# Sheet3.net
KiCad netlist of a schematic drawn in Altium Designer
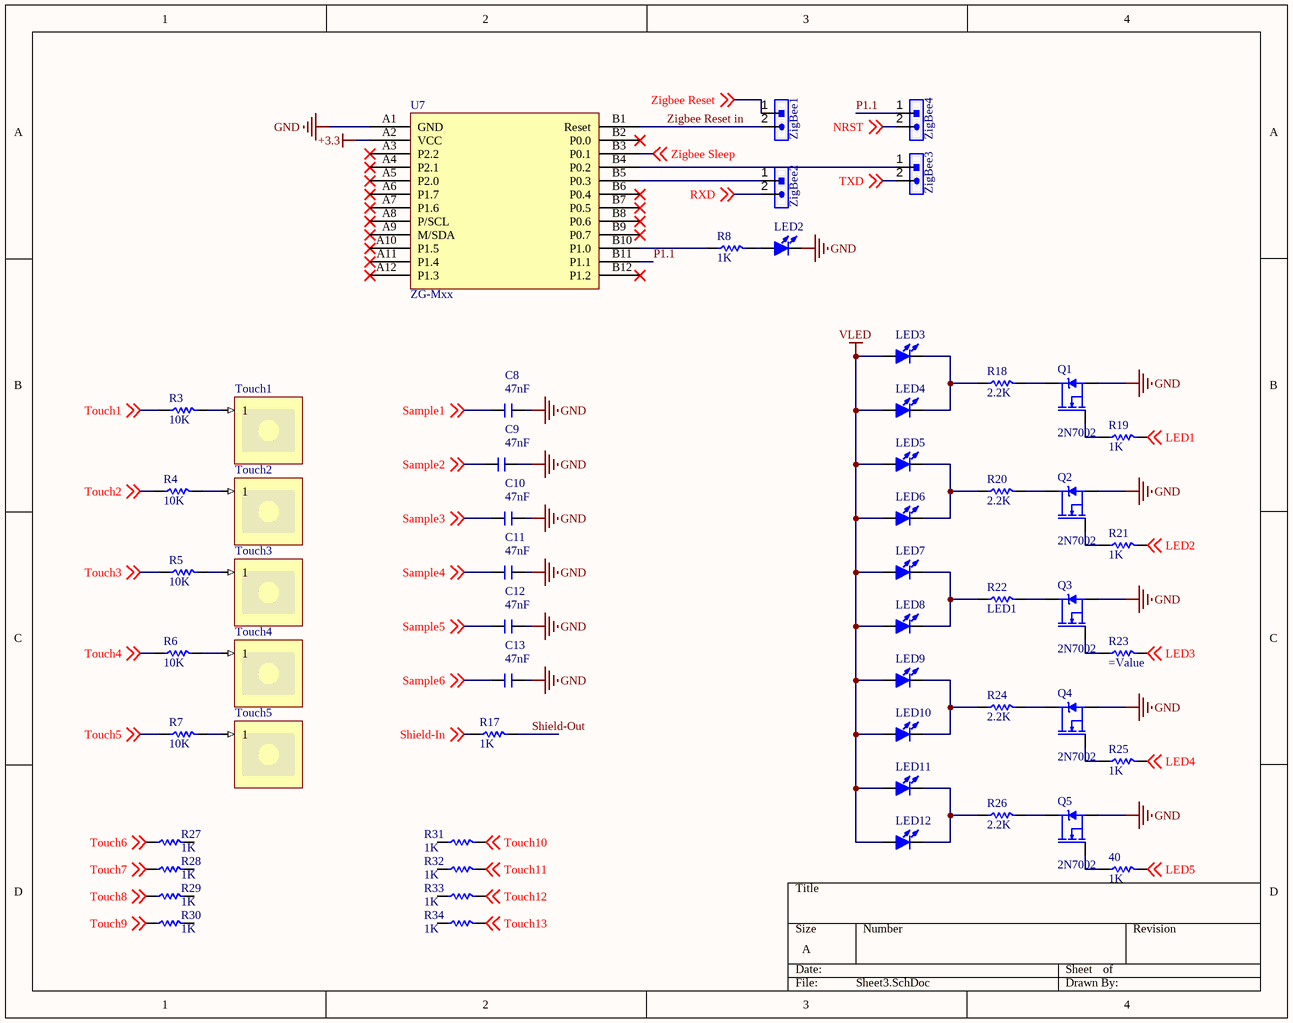
[diagram p0: Sheet3.SchDoc]

(export (version "E")
  (design (tool "Eeschema 10.0.6"))
  (components
    (comp (ref "40")
      (value "1K")
      (footprint "R 0805")
      (description "Chip resistor")
      (fields (field (name "版权归属") "源创客"))
      (libsource (lib "Passive (Resistor-Capacitor-Inductor-Veristor-Ferrite)") (part "R"))
    )
    (comp (ref "C8")
      (value "47nF")
      (footprint "C 0805")
      (description "Non-polar patch capacitor")
      (fields (field (name "版权归属") "源创客"))
      (libsource (lib "Passive (Resistor-Capacitor-Inductor-Veristor-Ferrite)") (part "C"))
    )
    (comp (ref "C9")
      (value "47nF")
      (footprint "C 0805")
      (description "Non-polar patch capacitor")
      (fields (field (name "版权归属") "源创客"))
      (libsource (lib "Passive (Resistor-Capacitor-Inductor-Veristor-Ferrite)") (part "C"))
    )
    (comp (ref "C10")
      (value "47nF")
      (footprint "C 0805")
      (description "Non-polar patch capacitor")
      (fields (field (name "版权归属") "源创客"))
      (libsource (lib "Passive (Resistor-Capacitor-Inductor-Veristor-Ferrite)") (part "C"))
    )
    (comp (ref "C11")
      (value "47nF")
      (footprint "C 0805")
      (description "Non-polar patch capacitor")
      (fields (field (name "版权归属") "源创客"))
      (libsource (lib "Passive (Resistor-Capacitor-Inductor-Veristor-Ferrite)") (part "C"))
    )
    (comp (ref "C12")
      (value "47nF")
      (footprint "C 0805")
      (description "Non-polar patch capacitor")
      (fields (field (name "版权归属") "源创客"))
      (libsource (lib "Passive (Resistor-Capacitor-Inductor-Veristor-Ferrite)") (part "C"))
    )
    (comp (ref "C13")
      (value "47nF")
      (footprint "C 0805")
      (description "Non-polar patch capacitor")
      (fields (field (name "版权归属") "源创客"))
      (libsource (lib "Passive (Resistor-Capacitor-Inductor-Veristor-Ferrite)") (part "C"))
    )
    (comp (ref "LED2")
      (value "LED-SMD")
      (footprint "LED 0805B")
      (description "Patch LED")
      (fields (field (name "版权归属") "源创客"))
      (libsource (lib "LED") (part "LED-SMD"))
    )
    (comp (ref "LED3")
      (value "~")
      (footprint "LED 3MM-B")
      (description "Plug-in LED")
      (fields (field (name "版权归属") "源创客"))
      (libsource (lib "LED") (part "LED-3MM"))
    )
    (comp (ref "LED4")
      (value "~")
      (footprint "LED 3MM-B")
      (description "Plug-in LED")
      (fields (field (name "版权归属") "源创客"))
      (libsource (lib "LED") (part "LED-3MM"))
    )
    (comp (ref "LED5")
      (value "~")
      (footprint "LED 3MM-B")
      (description "Plug-in LED")
      (fields (field (name "版权归属") "源创客"))
      (libsource (lib "LED") (part "LED-3MM"))
    )
    (comp (ref "LED6")
      (value "~")
      (footprint "LED 3MM-B")
      (description "Plug-in LED")
      (fields (field (name "版权归属") "源创客"))
      (libsource (lib "LED") (part "LED-3MM"))
    )
    (comp (ref "LED7")
      (value "~")
      (footprint "LED 3MM-B")
      (description "Plug-in LED")
      (fields (field (name "版权归属") "源创客"))
      (libsource (lib "LED") (part "LED-3MM"))
    )
    (comp (ref "LED8")
      (value "~")
      (footprint "LED 3MM-B")
      (description "Plug-in LED")
      (fields (field (name "版权归属") "源创客"))
      (libsource (lib "LED") (part "LED-3MM"))
    )
    (comp (ref "LED9")
      (value "~")
      (footprint "LED 3MM-B")
      (description "Plug-in LED")
      (fields (field (name "版权归属") "源创客"))
      (libsource (lib "LED") (part "LED-3MM"))
    )
    (comp (ref "LED10")
      (value "~")
      (footprint "LED 3MM-B")
      (description "Plug-in LED")
      (fields (field (name "版权归属") "源创客"))
      (libsource (lib "LED") (part "LED-3MM"))
    )
    (comp (ref "LED11")
      (value "~")
      (footprint "LED 3MM-B")
      (description "Plug-in LED")
      (fields (field (name "版权归属") "源创客"))
      (libsource (lib "LED") (part "LED-3MM"))
    )
    (comp (ref "LED12")
      (value "~")
      (footprint "LED 3MM-B")
      (description "Plug-in LED")
      (fields (field (name "版权归属") "源创客"))
      (libsource (lib "LED") (part "LED-3MM"))
    )
    (comp (ref "Q1")
      (value "2N7002")
      (footprint "SOT23-3")
      (description "N-Channel 60V 115mA (Tc) 225mW (Ta) Surface Mount SOT-23-3 (TO-236)")
      (fields (field (name "MF") "STMicroelectronics"))
      (libsource (lib "2N7002") (part "2N7002"))
    )
    (comp (ref "Q2")
      (value "2N7002")
      (footprint "SOT23-3")
      (description "N-Channel 60V 115mA (Tc) 225mW (Ta) Surface Mount SOT-23-3 (TO-236)")
      (fields (field (name "MF") "STMicroelectronics"))
      (libsource (lib "2N7002") (part "2N7002"))
    )
    (comp (ref "Q3")
      (value "2N7002")
      (footprint "SOT23-3")
      (description "N-Channel 60V 115mA (Tc) 225mW (Ta) Surface Mount SOT-23-3 (TO-236)")
      (fields (field (name "MF") "STMicroelectronics"))
      (libsource (lib "2N7002") (part "2N7002"))
    )
    (comp (ref "Q4")
      (value "2N7002")
      (footprint "SOT23-3")
      (description "N-Channel 60V 115mA (Tc) 225mW (Ta) Surface Mount SOT-23-3 (TO-236)")
      (fields (field (name "MF") "STMicroelectronics"))
      (libsource (lib "2N7002") (part "2N7002"))
    )
    (comp (ref "Q5")
      (value "2N7002")
      (footprint "SOT23-3")
      (description "N-Channel 60V 115mA (Tc) 225mW (Ta) Surface Mount SOT-23-3 (TO-236)")
      (fields (field (name "MF") "STMicroelectronics"))
      (libsource (lib "2N7002") (part "2N7002"))
    )
    (comp (ref "R3")
      (value "10K")
      (footprint "R 0805")
      (description "Chip resistor")
      (fields (field (name "版权归属") "源创客"))
      (libsource (lib "Passive (Resistor-Capacitor-Inductor-Veristor-Ferrite)") (part "R"))
    )
    (comp (ref "R4")
      (value "10K")
      (footprint "R 0805")
      (description "Chip resistor")
      (fields (field (name "版权归属") "源创客"))
      (libsource (lib "Passive (Resistor-Capacitor-Inductor-Veristor-Ferrite)") (part "R"))
    )
    (comp (ref "R5")
      (value "10K")
      (footprint "R 0805")
      (description "Chip resistor")
      (fields (field (name "版权归属") "源创客"))
      (libsource (lib "Passive (Resistor-Capacitor-Inductor-Veristor-Ferrite)") (part "R"))
    )
    (comp (ref "R6")
      (value "10K")
      (footprint "R 0805")
      (description "Chip resistor")
      (fields (field (name "版权归属") "源创客"))
      (libsource (lib "Passive (Resistor-Capacitor-Inductor-Veristor-Ferrite)") (part "R"))
    )
    (comp (ref "R7")
      (value "10K")
      (footprint "R 0805")
      (description "Chip resistor")
      (fields (field (name "版权归属") "源创客"))
      (libsource (lib "Passive (Resistor-Capacitor-Inductor-Veristor-Ferrite)") (part "R"))
    )
    (comp (ref "R8")
      (value "1K")
      (footprint "R 0805")
      (description "Chip resistor")
      (fields (field (name "版权归属") "源创客"))
      (libsource (lib "Passive (Resistor-Capacitor-Inductor-Veristor-Ferrite)") (part "R"))
    )
    (comp (ref "R17")
      (value "1K")
      (footprint "R 0805")
      (description "Chip resistor")
      (fields (field (name "版权归属") "源创客"))
      (libsource (lib "Passive (Resistor-Capacitor-Inductor-Veristor-Ferrite)") (part "R"))
    )
    (comp (ref "R18")
      (value "2.2K")
      (footprint "R 0805")
      (description "Chip resistor")
      (fields (field (name "版权归属") "源创客"))
      (libsource (lib "Passive (Resistor-Capacitor-Inductor-Veristor-Ferrite)") (part "R"))
    )
    (comp (ref "R19")
      (value "1K")
      (footprint "R 0805")
      (description "Chip resistor")
      (fields (field (name "版权归属") "源创客"))
      (libsource (lib "Passive (Resistor-Capacitor-Inductor-Veristor-Ferrite)") (part "R"))
    )
    (comp (ref "R20")
      (value "2.2K")
      (footprint "R 0805")
      (description "Chip resistor")
      (fields (field (name "版权归属") "源创客"))
      (libsource (lib "Passive (Resistor-Capacitor-Inductor-Veristor-Ferrite)") (part "R"))
    )
    (comp (ref "R21")
      (value "1K")
      (footprint "R 0805")
      (description "Chip resistor")
      (fields (field (name "版权归属") "源创客"))
      (libsource (lib "Passive (Resistor-Capacitor-Inductor-Veristor-Ferrite)") (part "R"))
    )
    (comp (ref "R22")
      (value "LED1")
      (footprint "R 0805")
      (description "Chip resistor")
      (fields (field (name "版权归属") "源创客"))
      (libsource (lib "Passive (Resistor-Capacitor-Inductor-Veristor-Ferrite)") (part "R"))
    )
    (comp (ref "R23")
      (value "~")
      (footprint "R 0805")
      (description "Chip resistor")
      (fields (field (name "版权归属") "源创客"))
      (libsource (lib "Passive (Resistor-Capacitor-Inductor-Veristor-Ferrite)") (part "R"))
    )
    (comp (ref "R24")
      (value "2.2K")
      (footprint "R 0805")
      (description "Chip resistor")
      (fields (field (name "版权归属") "源创客"))
      (libsource (lib "Passive (Resistor-Capacitor-Inductor-Veristor-Ferrite)") (part "R"))
    )
    (comp (ref "R25")
      (value "1K")
      (footprint "R 0805")
      (description "Chip resistor")
      (fields (field (name "版权归属") "源创客"))
      (libsource (lib "Passive (Resistor-Capacitor-Inductor-Veristor-Ferrite)") (part "R"))
    )
    (comp (ref "R26")
      (value "2.2K")
      (footprint "R 0805")
      (description "Chip resistor")
      (fields (field (name "版权归属") "源创客"))
      (libsource (lib "Passive (Resistor-Capacitor-Inductor-Veristor-Ferrite)") (part "R"))
    )
    (comp (ref "R27")
      (value "1K")
      (footprint "R 0805")
      (description "Chip resistor")
      (fields (field (name "版权归属") "源创客"))
      (libsource (lib "Passive (Resistor-Capacitor-Inductor-Veristor-Ferrite)") (part "R"))
    )
    (comp (ref "R28")
      (value "1K")
      (footprint "R 0805")
      (description "Chip resistor")
      (fields (field (name "版权归属") "源创客"))
      (libsource (lib "Passive (Resistor-Capacitor-Inductor-Veristor-Ferrite)") (part "R"))
    )
    (comp (ref "R29")
      (value "1K")
      (footprint "R 0805")
      (description "Chip resistor")
      (fields (field (name "版权归属") "源创客"))
      (libsource (lib "Passive (Resistor-Capacitor-Inductor-Veristor-Ferrite)") (part "R"))
    )
    (comp (ref "R30")
      (value "1K")
      (footprint "R 0805")
      (description "Chip resistor")
      (fields (field (name "版权归属") "源创客"))
      (libsource (lib "Passive (Resistor-Capacitor-Inductor-Veristor-Ferrite)") (part "R"))
    )
    (comp (ref "R31")
      (value "1K")
      (footprint "R 0805")
      (description "Chip resistor")
      (fields (field (name "版权归属") "源创客"))
      (libsource (lib "Passive (Resistor-Capacitor-Inductor-Veristor-Ferrite)") (part "R"))
    )
    (comp (ref "R32")
      (value "1K")
      (footprint "R 0805")
      (description "Chip resistor")
      (fields (field (name "版权归属") "源创客"))
      (libsource (lib "Passive (Resistor-Capacitor-Inductor-Veristor-Ferrite)") (part "R"))
    )
    (comp (ref "R33")
      (value "1K")
      (footprint "R 0805")
      (description "Chip resistor")
      (fields (field (name "版权归属") "源创客"))
      (libsource (lib "Passive (Resistor-Capacitor-Inductor-Veristor-Ferrite)") (part "R"))
    )
    (comp (ref "R34")
      (value "1K")
      (footprint "R 0805")
      (description "Chip resistor")
      (fields (field (name "版权归属") "源创客"))
      (libsource (lib "Passive (Resistor-Capacitor-Inductor-Veristor-Ferrite)") (part "R"))
    )
    (comp (ref "Touch1")
      (value "CircularButton")
      (libsource (lib "Cypress CapSense") (part "CircularButton"))
    )
    (comp (ref "Touch2")
      (value "CircularButton")
      (libsource (lib "Cypress CapSense") (part "CircularButton"))
    )
    (comp (ref "Touch3")
      (value "CircularButton")
      (libsource (lib "Cypress CapSense") (part "CircularButton"))
    )
    (comp (ref "Touch4")
      (value "CircularButton")
      (libsource (lib "Cypress CapSense") (part "CircularButton"))
    )
    (comp (ref "Touch5")
      (value "CircularButton")
      (libsource (lib "Cypress CapSense") (part "CircularButton"))
    )
    (comp (ref "U7") (value "ZG-Mxx") (footprint "XBee") (libsource (lib "XBee") (part "XBee")))
    (comp (ref "ZigBee1")
      (value "HDR-1X2")
      (footprint "HDR-1X2")
      (description "2P Connector")
      (fields (field (name "版权归属") "源创客"))
      (libsource (lib "Connectors") (part "Header 2"))
    )
    (comp (ref "ZigBee2")
      (value "HDR-1X2")
      (footprint "HDR-1X2")
      (description "2P Connector")
      (fields (field (name "版权归属") "源创客"))
      (libsource (lib "Connectors") (part "Header 2"))
    )
    (comp (ref "ZigBee3")
      (value "HDR-1X2")
      (footprint "HDR-1X2")
      (description "2P Connector")
      (fields (field (name "版权归属") "源创客"))
      (libsource (lib "Connectors") (part "Header 2"))
    )
    (comp (ref "ZigBee4")
      (value "HDR-1X2")
      (footprint "HDR-1X2")
      (description "2P Connector")
      (fields (field (name "版权归属") "源创客"))
      (libsource (lib "Connectors") (part "Header 2"))
    )
  )
  (nets
    (net (code "1") (name "+3.3") (class "Default")
      (node (ref "U7") (pin "A2") (pinfunction "VCC_A2") (pintype "passive"))
    )
    (net (code "2") (name "/P1.1") (class "Default")
      (node (ref "U7") (pin "B11") (pinfunction "P1.1_B11") (pintype "passive"))
      (node (ref "ZigBee4") (pin "1") (pintype "passive"))
    )
    (net (code "3") (name "/Shield-Out") (class "Default")
      (node (ref "R17") (pin "2") (pinfunction "2_2") (pintype "passive"))
    )
    (net (code "4") (name "/Zigbee Reset in") (class "Default")
      (node (ref "U7") (pin "B1") (pinfunction "Reset_B1") (pintype "passive"))
      (node (ref "ZigBee1") (pin "2") (pintype "passive"))
    )
    (net (code "5") (name "GND") (class "Default")
      (node (ref "C10") (pin "2") (pinfunction "2_2") (pintype "passive"))
      (node (ref "C11") (pin "2") (pinfunction "2_2") (pintype "passive"))
      (node (ref "C12") (pin "2") (pinfunction "2_2") (pintype "passive"))
      (node (ref "C13") (pin "2") (pinfunction "2_2") (pintype "passive"))
      (node (ref "C8") (pin "2") (pinfunction "2_2") (pintype "passive"))
      (node (ref "C9") (pin "2") (pinfunction "2_2") (pintype "passive"))
      (node (ref "LED2") (pin "2") (pinfunction "K_2") (pintype "passive"))
      (node (ref "Q1") (pin "2") (pinfunction "S_2") (pintype "bidirectional"))
      (node (ref "Q2") (pin "2") (pinfunction "S_2") (pintype "bidirectional"))
      (node (ref "Q3") (pin "2") (pinfunction "S_2") (pintype "bidirectional"))
      (node (ref "Q4") (pin "2") (pinfunction "S_2") (pintype "bidirectional"))
      (node (ref "Q5") (pin "2") (pinfunction "S_2") (pintype "bidirectional"))
      (node (ref "U7") (pin "A1") (pinfunction "GND_A1") (pintype "passive"))
    )
    (net (code "6") (name "LED1") (class "Default")
      (node (ref "R19") (pin "2") (pinfunction "2_2") (pintype "passive"))
    )
    (net (code "7") (name "LED2") (class "Default")
      (node (ref "R21") (pin "2") (pinfunction "2_2") (pintype "passive"))
    )
    (net (code "8") (name "LED3") (class "Default")
      (node (ref "R23") (pin "2") (pinfunction "2_2") (pintype "passive"))
    )
    (net (code "9") (name "LED4") (class "Default")
      (node (ref "R25") (pin "2") (pinfunction "2_2") (pintype "passive"))
    )
    (net (code "10") (name "LED5") (class "Default")
      (node (ref "40") (pin "2") (pinfunction "2_2") (pintype "passive"))
    )
    (net (code "11") (name "NRST") (class "Default") (node (ref "ZigBee4") (pin "2") (pintype "passive")))
    (net (code "12") (name "Net-(LED2-A)") (class "Default")
      (node (ref "LED2") (pin "1") (pinfunction "A_1") (pintype "passive"))
      (node (ref "R8") (pin "2") (pinfunction "2_2") (pintype "passive"))
    )
    (net (code "13") (name "Net-(LED3-K)") (class "Default")
      (node (ref "LED3") (pin "2") (pinfunction "K_2") (pintype "passive"))
      (node (ref "LED4") (pin "2") (pinfunction "K_2") (pintype "passive"))
      (node (ref "R18") (pin "1") (pinfunction "1_1") (pintype "passive"))
    )
    (net (code "14") (name "Net-(LED5-K)") (class "Default")
      (node (ref "LED5") (pin "2") (pinfunction "K_2") (pintype "passive"))
      (node (ref "LED6") (pin "2") (pinfunction "K_2") (pintype "passive"))
      (node (ref "R20") (pin "1") (pinfunction "1_1") (pintype "passive"))
    )
    (net (code "15") (name "Net-(LED7-K)") (class "Default")
      (node (ref "LED7") (pin "2") (pinfunction "K_2") (pintype "passive"))
      (node (ref "LED8") (pin "2") (pinfunction "K_2") (pintype "passive"))
      (node (ref "R22") (pin "1") (pinfunction "1_1") (pintype "passive"))
    )
    (net (code "16") (name "Net-(LED10-K)") (class "Default")
      (node (ref "LED10") (pin "2") (pinfunction "K_2") (pintype "passive"))
      (node (ref "LED9") (pin "2") (pinfunction "K_2") (pintype "passive"))
      (node (ref "R24") (pin "1") (pinfunction "1_1") (pintype "passive"))
    )
    (net (code "17") (name "Net-(LED11-K)") (class "Default")
      (node (ref "LED11") (pin "2") (pinfunction "K_2") (pintype "passive"))
      (node (ref "LED12") (pin "2") (pinfunction "K_2") (pintype "passive"))
      (node (ref "R26") (pin "1") (pinfunction "1_1") (pintype "passive"))
    )
    (net (code "18") (name "Net-(Q1-D)") (class "Default")
      (node (ref "Q1") (pin "3") (pinfunction "D_3") (pintype "bidirectional"))
      (node (ref "R18") (pin "2") (pinfunction "2_2") (pintype "passive"))
    )
    (net (code "19") (name "Net-(Q1-G)") (class "Default")
      (node (ref "Q1") (pin "1") (pinfunction "G_1") (pintype "bidirectional"))
      (node (ref "R19") (pin "1") (pinfunction "1_1") (pintype "passive"))
    )
    (net (code "20") (name "Net-(Q2-D)") (class "Default")
      (node (ref "Q2") (pin "3") (pinfunction "D_3") (pintype "bidirectional"))
      (node (ref "R20") (pin "2") (pinfunction "2_2") (pintype "passive"))
    )
    (net (code "21") (name "Net-(Q2-G)") (class "Default")
      (node (ref "Q2") (pin "1") (pinfunction "G_1") (pintype "bidirectional"))
      (node (ref "R21") (pin "1") (pinfunction "1_1") (pintype "passive"))
    )
    (net (code "22") (name "Net-(Q3-D)") (class "Default")
      (node (ref "Q3") (pin "3") (pinfunction "D_3") (pintype "bidirectional"))
      (node (ref "R22") (pin "2") (pinfunction "2_2") (pintype "passive"))
    )
    (net (code "23") (name "Net-(Q3-G)") (class "Default")
      (node (ref "Q3") (pin "1") (pinfunction "G_1") (pintype "bidirectional"))
      (node (ref "R23") (pin "1") (pinfunction "1_1") (pintype "passive"))
    )
    (net (code "24") (name "Net-(Q4-D)") (class "Default")
      (node (ref "Q4") (pin "3") (pinfunction "D_3") (pintype "bidirectional"))
      (node (ref "R24") (pin "2") (pinfunction "2_2") (pintype "passive"))
    )
    (net (code "25") (name "Net-(Q4-G)") (class "Default")
      (node (ref "Q4") (pin "1") (pinfunction "G_1") (pintype "bidirectional"))
      (node (ref "R25") (pin "1") (pinfunction "1_1") (pintype "passive"))
    )
    (net (code "26") (name "Net-(Q5-D)") (class "Default")
      (node (ref "Q5") (pin "3") (pinfunction "D_3") (pintype "bidirectional"))
      (node (ref "R26") (pin "2") (pinfunction "2_2") (pintype "passive"))
    )
    (net (code "27") (name "Net-(Q5-G)") (class "Default")
      (node (ref "40") (pin "1") (pinfunction "1_1") (pintype "passive"))
      (node (ref "Q5") (pin "1") (pinfunction "G_1") (pintype "bidirectional"))
    )
    (net (code "28") (name "Net-(R3-Pad2)") (class "Default")
      (node (ref "R3") (pin "2") (pinfunction "2_2") (pintype "passive"))
      (node (ref "Touch1") (pin "1") (pinfunction "1_1") (pintype "input"))
    )
    (net (code "29") (name "Net-(R4-Pad2)") (class "Default")
      (node (ref "R4") (pin "2") (pinfunction "2_2") (pintype "passive"))
      (node (ref "Touch2") (pin "1") (pinfunction "1_1") (pintype "input"))
    )
    (net (code "30") (name "Net-(R5-Pad2)") (class "Default")
      (node (ref "R5") (pin "2") (pinfunction "2_2") (pintype "passive"))
      (node (ref "Touch3") (pin "1") (pinfunction "1_1") (pintype "input"))
    )
    (net (code "31") (name "Net-(R6-Pad2)") (class "Default")
      (node (ref "R6") (pin "2") (pinfunction "2_2") (pintype "passive"))
      (node (ref "Touch4") (pin "1") (pinfunction "1_1") (pintype "input"))
    )
    (net (code "32") (name "Net-(R7-Pad2)") (class "Default")
      (node (ref "R7") (pin "2") (pinfunction "2_2") (pintype "passive"))
      (node (ref "Touch5") (pin "1") (pinfunction "1_1") (pintype "input"))
    )
    (net (code "33") (name "Net-(U7-P0.2)") (class "Default")
      (node (ref "U7") (pin "B4") (pinfunction "P0.2_B4") (pintype "passive"))
      (node (ref "ZigBee3") (pin "1") (pintype "passive"))
    )
    (net (code "34") (name "Net-(U7-P0.3)") (class "Default")
      (node (ref "U7") (pin "B5") (pinfunction "P0.3_B5") (pintype "passive"))
      (node (ref "ZigBee2") (pin "1") (pintype "passive"))
    )
    (net (code "35") (name "Net-(U7-P1.0)") (class "Default")
      (node (ref "R8") (pin "1") (pinfunction "1_1") (pintype "passive"))
      (node (ref "U7") (pin "B10") (pinfunction "P1.0_B10") (pintype "passive"))
    )
    (net (code "36") (name "RXD") (class "Default") (node (ref "ZigBee2") (pin "2") (pintype "passive")))
    (net (code "37") (name "Sample1") (class "Default")
      (node (ref "C8") (pin "1") (pinfunction "1_1") (pintype "passive"))
    )
    (net (code "38") (name "Sample2") (class "Default")
      (node (ref "C9") (pin "1") (pinfunction "1_1") (pintype "passive"))
    )
    (net (code "39") (name "Sample3") (class "Default")
      (node (ref "C10") (pin "1") (pinfunction "1_1") (pintype "passive"))
    )
    (net (code "40") (name "Sample4") (class "Default")
      (node (ref "C11") (pin "1") (pinfunction "1_1") (pintype "passive"))
    )
    (net (code "41") (name "Sample5") (class "Default")
      (node (ref "C12") (pin "1") (pinfunction "1_1") (pintype "passive"))
    )
    (net (code "42") (name "Sample6") (class "Default")
      (node (ref "C13") (pin "1") (pinfunction "1_1") (pintype "passive"))
    )
    (net (code "43") (name "Shield-In") (class "Default")
      (node (ref "R17") (pin "1") (pinfunction "1_1") (pintype "passive"))
    )
    (net (code "44") (name "TXD") (class "Default") (node (ref "ZigBee3") (pin "2") (pintype "passive")))
    (net (code "45") (name "Touch1") (class "Default")
      (node (ref "R3") (pin "1") (pinfunction "1_1") (pintype "passive"))
    )
    (net (code "46") (name "Touch2") (class "Default")
      (node (ref "R4") (pin "1") (pinfunction "1_1") (pintype "passive"))
    )
    (net (code "47") (name "Touch3") (class "Default")
      (node (ref "R5") (pin "1") (pinfunction "1_1") (pintype "passive"))
    )
    (net (code "48") (name "Touch4") (class "Default")
      (node (ref "R6") (pin "1") (pinfunction "1_1") (pintype "passive"))
    )
    (net (code "49") (name "Touch5") (class "Default")
      (node (ref "R7") (pin "1") (pinfunction "1_1") (pintype "passive"))
    )
    (net (code "50") (name "Touch6") (class "Default")
      (node (ref "R27") (pin "1") (pinfunction "1_1") (pintype "passive"))
    )
    (net (code "51") (name "Touch7") (class "Default")
      (node (ref "R28") (pin "1") (pinfunction "1_1") (pintype "passive"))
    )
    (net (code "52") (name "Touch8") (class "Default")
      (node (ref "R29") (pin "1") (pinfunction "1_1") (pintype "passive"))
    )
    (net (code "53") (name "Touch9") (class "Default")
      (node (ref "R30") (pin "1") (pinfunction "1_1") (pintype "passive"))
    )
    (net (code "54") (name "Touch10") (class "Default")
      (node (ref "R31") (pin "2") (pinfunction "2_2") (pintype "passive"))
    )
    (net (code "55") (name "Touch11") (class "Default")
      (node (ref "R32") (pin "2") (pinfunction "2_2") (pintype "passive"))
    )
    (net (code "56") (name "Touch12") (class "Default")
      (node (ref "R33") (pin "2") (pinfunction "2_2") (pintype "passive"))
    )
    (net (code "57") (name "Touch13") (class "Default")
      (node (ref "R34") (pin "2") (pinfunction "2_2") (pintype "passive"))
    )
    (net (code "58") (name "VLED") (class "Default")
      (node (ref "LED10") (pin "1") (pinfunction "A_1") (pintype "passive"))
      (node (ref "LED11") (pin "1") (pinfunction "A_1") (pintype "passive"))
      (node (ref "LED12") (pin "1") (pinfunction "A_1") (pintype "passive"))
      (node (ref "LED3") (pin "1") (pinfunction "A_1") (pintype "passive"))
      (node (ref "LED4") (pin "1") (pinfunction "A_1") (pintype "passive"))
      (node (ref "LED5") (pin "1") (pinfunction "A_1") (pintype "passive"))
      (node (ref "LED6") (pin "1") (pinfunction "A_1") (pintype "passive"))
      (node (ref "LED7") (pin "1") (pinfunction "A_1") (pintype "passive"))
      (node (ref "LED8") (pin "1") (pinfunction "A_1") (pintype "passive"))
      (node (ref "LED9") (pin "1") (pinfunction "A_1") (pintype "passive"))
    )
    (net (code "59") (name "Zigbee Reset") (class "Default")
      (node (ref "ZigBee1") (pin "1") (pintype "passive"))
    )
    (net (code "60") (name "Zigbee Sleep") (class "Default")
      (node (ref "U7") (pin "B3") (pinfunction "P0.1_B3") (pintype "passive"))
    )
    (net (code "61") (name "unconnected-(R27-Pad2)") (class "Default")
      (node (ref "R27") (pin "2") (pinfunction "2_2") (pintype "passive"))
    )
    (net (code "62") (name "unconnected-(R28-Pad2)") (class "Default")
      (node (ref "R28") (pin "2") (pinfunction "2_2") (pintype "passive"))
    )
    (net (code "63") (name "unconnected-(R29-Pad2)") (class "Default")
      (node (ref "R29") (pin "2") (pinfunction "2_2") (pintype "passive"))
    )
    (net (code "64") (name "unconnected-(R30-Pad2)") (class "Default")
      (node (ref "R30") (pin "2") (pinfunction "2_2") (pintype "passive"))
    )
    (net (code "65") (name "unconnected-(R31-Pad1)") (class "Default")
      (node (ref "R31") (pin "1") (pinfunction "1_1") (pintype "passive"))
    )
    (net (code "66") (name "unconnected-(R32-Pad1)") (class "Default")
      (node (ref "R32") (pin "1") (pinfunction "1_1") (pintype "passive"))
    )
    (net (code "67") (name "unconnected-(R33-Pad1)") (class "Default")
      (node (ref "R33") (pin "1") (pinfunction "1_1") (pintype "passive"))
    )
    (net (code "68") (name "unconnected-(R34-Pad1)") (class "Default")
      (node (ref "R34") (pin "1") (pinfunction "1_1") (pintype "passive"))
    )
    (net (code "69") (name "unconnected-(U7-M{slash}SDA-PadA9)") (class "Default")
      (node (ref "U7") (pin "A9") (pinfunction "M/SDA_A9") (pintype "passive+no_connect"))
    )
    (net (code "70") (name "unconnected-(U7-P0.0-PadB2)") (class "Default")
      (node (ref "U7") (pin "B2") (pinfunction "P0.0_B2") (pintype "passive+no_connect"))
    )
    (net (code "71") (name "unconnected-(U7-P0.4-PadB6)") (class "Default")
      (node (ref "U7") (pin "B6") (pinfunction "P0.4_B6") (pintype "passive+no_connect"))
    )
    (net (code "72") (name "unconnected-(U7-P0.5-PadB7)") (class "Default")
      (node (ref "U7") (pin "B7") (pinfunction "P0.5_B7") (pintype "passive+no_connect"))
    )
    (net (code "73") (name "unconnected-(U7-P0.6-PadB8)") (class "Default")
      (node (ref "U7") (pin "B8") (pinfunction "P0.6_B8") (pintype "passive+no_connect"))
    )
    (net (code "74") (name "unconnected-(U7-P0.7-PadB9)") (class "Default")
      (node (ref "U7") (pin "B9") (pinfunction "P0.7_B9") (pintype "passive+no_connect"))
    )
    (net (code "75") (name "unconnected-(U7-P1.2-PadB12)") (class "Default")
      (node (ref "U7") (pin "B12") (pinfunction "P1.2_B12") (pintype "passive+no_connect"))
    )
    (net (code "76") (name "unconnected-(U7-P1.3-PadA12)") (class "Default")
      (node (ref "U7") (pin "A12") (pinfunction "P1.3_A12") (pintype "passive+no_connect"))
    )
    (net (code "77") (name "unconnected-(U7-P1.4-PadA11)") (class "Default")
      (node (ref "U7") (pin "A11") (pinfunction "P1.4_A11") (pintype "passive+no_connect"))
    )
    (net (code "78") (name "unconnected-(U7-P1.5-PadA10)") (class "Default")
      (node (ref "U7") (pin "A10") (pinfunction "P1.5_A10") (pintype "passive+no_connect"))
    )
    (net (code "79") (name "unconnected-(U7-P1.6-PadA7)") (class "Default")
      (node (ref "U7") (pin "A7") (pinfunction "P1.6_A7") (pintype "passive+no_connect"))
    )
    (net (code "80") (name "unconnected-(U7-P1.7-PadA6)") (class "Default")
      (node (ref "U7") (pin "A6") (pinfunction "P1.7_A6") (pintype "passive+no_connect"))
    )
    (net (code "81") (name "unconnected-(U7-P2.0-PadA5)") (class "Default")
      (node (ref "U7") (pin "A5") (pinfunction "P2.0_A5") (pintype "passive+no_connect"))
    )
    (net (code "82") (name "unconnected-(U7-P2.1-PadA4)") (class "Default")
      (node (ref "U7") (pin "A4") (pinfunction "P2.1_A4") (pintype "passive+no_connect"))
    )
    (net (code "83") (name "unconnected-(U7-P2.2-PadA3)") (class "Default")
      (node (ref "U7") (pin "A3") (pinfunction "P2.2_A3") (pintype "passive+no_connect"))
    )
    (net (code "84") (name "unconnected-(U7-P{slash}SCL-PadA8)") (class "Default")
      (node (ref "U7") (pin "A8") (pinfunction "P/SCL_A8") (pintype "passive+no_connect"))
    )
  )
)
